# watchdog_timer.net
KiCad netlist of a schematic drawn in EAGLE
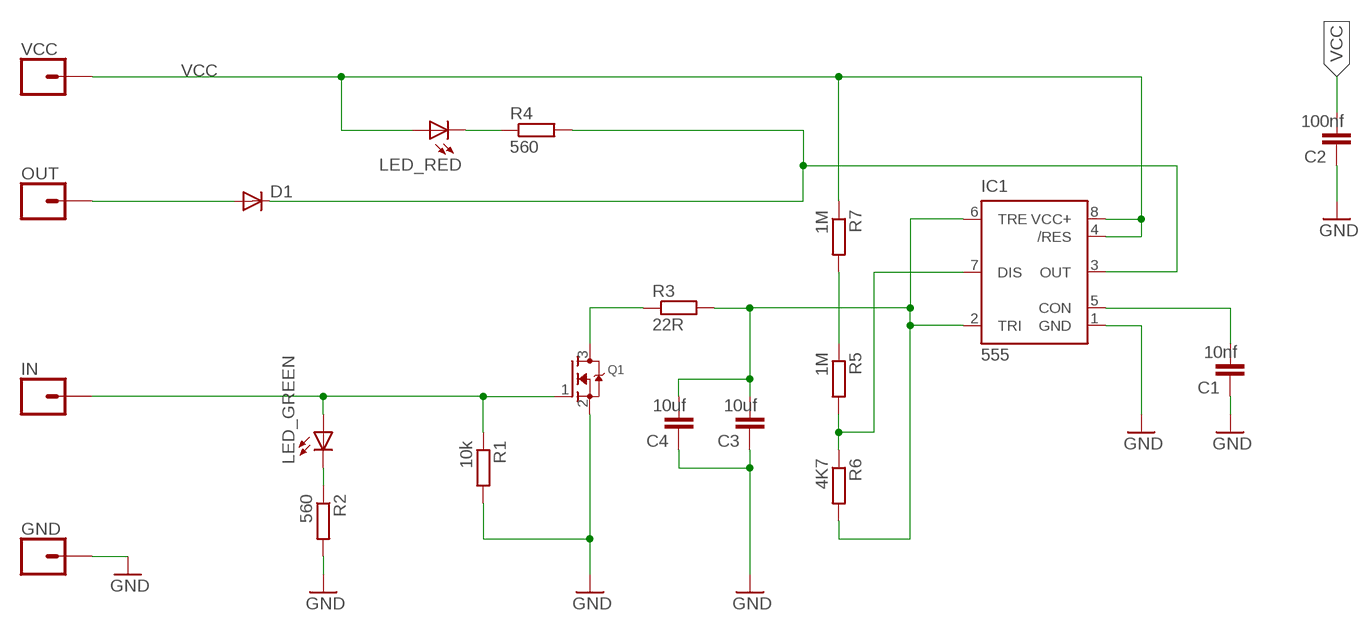
[diagram p0: schematic, sheet 1]

(export (version "E")
  (design (tool "Eeschema 10.0.6"))
  (components
    (comp (ref "C1")
      (value "10nf")
      (footprint "eagle-import:C1206")
      (libsource (lib "eagle-import") (part "C-EUC1206"))
    )
    (comp (ref "C2")
      (value "100nf")
      (footprint "eagle-import:C1206")
      (libsource (lib "eagle-import") (part "C-EUC1206"))
    )
    (comp (ref "C3")
      (value "10uf")
      (footprint "eagle-import:C1206")
      (libsource (lib "eagle-import") (part "C-EUC1206"))
    )
    (comp (ref "C4")
      (value "10uf")
      (footprint "eagle-import:C1206")
      (libsource (lib "eagle-import") (part "C-EUC1206"))
    )
    (comp (ref "D1")
      (value "DIODE-SOD323-W")
      (footprint "eagle-import:SOD323-W")
      (libsource (lib "eagle-import") (part "DIODE-SOD323-W"))
    )
    (comp (ref "GND")
      (value "CONN_01")
      (footprint "eagle-import:1X01")
      (libsource (lib "eagle-import") (part "CONN_01"))
    )
    (comp (ref "IC1")
      (value "555")
      (footprint "eagle-import:SO08")
      (libsource (lib "eagle-import") (part "555D"))
    )
    (comp (ref "IN")
      (value "CONN_01")
      (footprint "eagle-import:1X01")
      (libsource (lib "eagle-import") (part "CONN_01"))
    )
    (comp (ref "LED_GREEN")
      (value "LEDSML0805")
      (footprint "eagle-import:SML0805")
      (libsource (lib "eagle-import") (part "LEDSML0805"))
    )
    (comp (ref "LED_RED")
      (value "LEDSML0805")
      (footprint "eagle-import:SML0805")
      (libsource (lib "eagle-import") (part "LEDSML0805"))
    )
    (comp (ref "OUT")
      (value "CONN_01")
      (footprint "eagle-import:1X01")
      (libsource (lib "eagle-import") (part "CONN_01"))
    )
    (comp (ref "Q1")
      (value "MOSFET-NREFLOW")
      (footprint "eagle-import:SOT23")
      (libsource (lib "eagle-import") (part "MOSFET-NREFLOW"))
    )
    (comp (ref "R1")
      (value "10k")
      (footprint "eagle-import:M0805")
      (libsource (lib "eagle-import") (part "R-EU_M0805"))
    )
    (comp (ref "R2")
      (value "560")
      (footprint "eagle-import:M0805")
      (libsource (lib "eagle-import") (part "R-EU_M0805"))
    )
    (comp (ref "R3")
      (value "22R")
      (footprint "eagle-import:M0805")
      (libsource (lib "eagle-import") (part "R-EU_M0805"))
    )
    (comp (ref "R4")
      (value "560")
      (footprint "eagle-import:M0805")
      (libsource (lib "eagle-import") (part "R-EU_M0805"))
    )
    (comp (ref "R5")
      (value "1M")
      (footprint "eagle-import:M0805")
      (libsource (lib "eagle-import") (part "R-EU_M0805"))
    )
    (comp (ref "R6")
      (value "4K7")
      (footprint "eagle-import:M0805")
      (libsource (lib "eagle-import") (part "R-EU_M0805"))
    )
    (comp (ref "R7")
      (value "1M")
      (footprint "eagle-import:M0805")
      (libsource (lib "eagle-import") (part "R-EU_M0805"))
    )
    (comp (ref "VCC")
      (value "CONN_01")
      (footprint "eagle-import:1X01")
      (libsource (lib "eagle-import") (part "CONN_01"))
    )
  )
  (nets
    (net (code "1") (name "GND") (class "Default")
      (node (ref "C1") (pin "1") (pinfunction "1_1") (pintype "passive"))
      (node (ref "C2") (pin "1") (pinfunction "1_1") (pintype "passive"))
      (node (ref "C3") (pin "1") (pinfunction "1_1") (pintype "passive"))
      (node (ref "C4") (pin "1") (pinfunction "1_1") (pintype "passive"))
      (node (ref "GND") (pin "1") (pinfunction "1_1") (pintype "passive"))
      (node (ref "IC1") (pin "1") (pinfunction "GND_1") (pintype "power_in"))
      (node (ref "Q1") (pin "2") (pinfunction "S_2") (pintype "bidirectional"))
      (node (ref "R1") (pin "2") (pinfunction "2_2") (pintype "passive"))
      (node (ref "R2") (pin "2") (pinfunction "2_2") (pintype "passive"))
    )
    (net (code "2") (name "Net-(D1-PadA)") (class "Default")
      (node (ref "D1") (pin "A") (pinfunction "A_A") (pintype "passive"))
      (node (ref "OUT") (pin "1") (pinfunction "1_1") (pintype "passive"))
    )
    (net (code "3") (name "Net-(IC1-CON)") (class "Default")
      (node (ref "C1") (pin "2") (pinfunction "2_2") (pintype "passive"))
      (node (ref "IC1") (pin "5") (pinfunction "CON_5") (pintype "input"))
    )
    (net (code "4") (name "Net-(IC1-DIS)") (class "Default")
      (node (ref "IC1") (pin "7") (pinfunction "DIS_7") (pintype "input"))
      (node (ref "R5") (pin "2") (pinfunction "2_2") (pintype "passive"))
      (node (ref "R6") (pin "1") (pinfunction "1_1") (pintype "passive"))
    )
    (net (code "5") (name "Net-(IC1-OUT)") (class "Default")
      (node (ref "D1") (pin "C") (pinfunction "C_C") (pintype "passive"))
      (node (ref "IC1") (pin "3") (pinfunction "OUT_3") (pintype "output"))
      (node (ref "R4") (pin "2") (pinfunction "2_2") (pintype "passive"))
    )
    (net (code "6") (name "Net-(IC1-TRE)") (class "Default")
      (node (ref "C3") (pin "2") (pinfunction "2_2") (pintype "passive"))
      (node (ref "C4") (pin "2") (pinfunction "2_2") (pintype "passive"))
      (node (ref "IC1") (pin "2") (pinfunction "TRI_2") (pintype "input"))
      (node (ref "IC1") (pin "6") (pinfunction "TRE_6") (pintype "input"))
      (node (ref "R3") (pin "2") (pinfunction "2_2") (pintype "passive"))
      (node (ref "R6") (pin "2") (pinfunction "2_2") (pintype "passive"))
    )
    (net (code "7") (name "Net-(LED_GREEN-PadC)") (class "Default")
      (node (ref "LED_GREEN") (pin "C") (pinfunction "C_C") (pintype "passive"))
      (node (ref "R2") (pin "1") (pinfunction "1_1") (pintype "passive"))
    )
    (net (code "8") (name "Net-(LED_RED-PadC)") (class "Default")
      (node (ref "LED_RED") (pin "C") (pinfunction "C_C") (pintype "passive"))
      (node (ref "R4") (pin "1") (pinfunction "1_1") (pintype "passive"))
    )
    (net (code "9") (name "Net-(Q1-D)") (class "Default")
      (node (ref "Q1") (pin "3") (pinfunction "D_3") (pintype "bidirectional"))
      (node (ref "R3") (pin "1") (pinfunction "1_1") (pintype "passive"))
    )
    (net (code "10") (name "Net-(Q1-G)") (class "Default")
      (node (ref "IN") (pin "1") (pinfunction "1_1") (pintype "passive"))
      (node (ref "LED_GREEN") (pin "A") (pinfunction "A_A") (pintype "passive"))
      (node (ref "Q1") (pin "1") (pinfunction "G_1") (pintype "bidirectional"))
      (node (ref "R1") (pin "1") (pinfunction "1_1") (pintype "passive"))
    )
    (net (code "11") (name "Net-(R5-Pad1)") (class "Default")
      (node (ref "R5") (pin "1") (pinfunction "1_1") (pintype "passive"))
      (node (ref "R7") (pin "2") (pinfunction "2_2") (pintype "passive"))
    )
    (net (code "12") (name "VCC") (class "Default")
      (node (ref "C2") (pin "2") (pinfunction "2_2") (pintype "passive"))
      (node (ref "IC1") (pin "4") (pinfunction "/RES_4") (pintype "input"))
      (node (ref "IC1") (pin "8") (pinfunction "VCC+_8") (pintype "power_in"))
      (node (ref "LED_RED") (pin "A") (pinfunction "A_A") (pintype "passive"))
      (node (ref "R7") (pin "1") (pinfunction "1_1") (pintype "passive"))
      (node (ref "VCC") (pin "1") (pinfunction "1_1") (pintype "passive"))
    )
  )
)
